# ControlDevBoard.net
KiCad netlist of a schematic drawn in EasyEDA
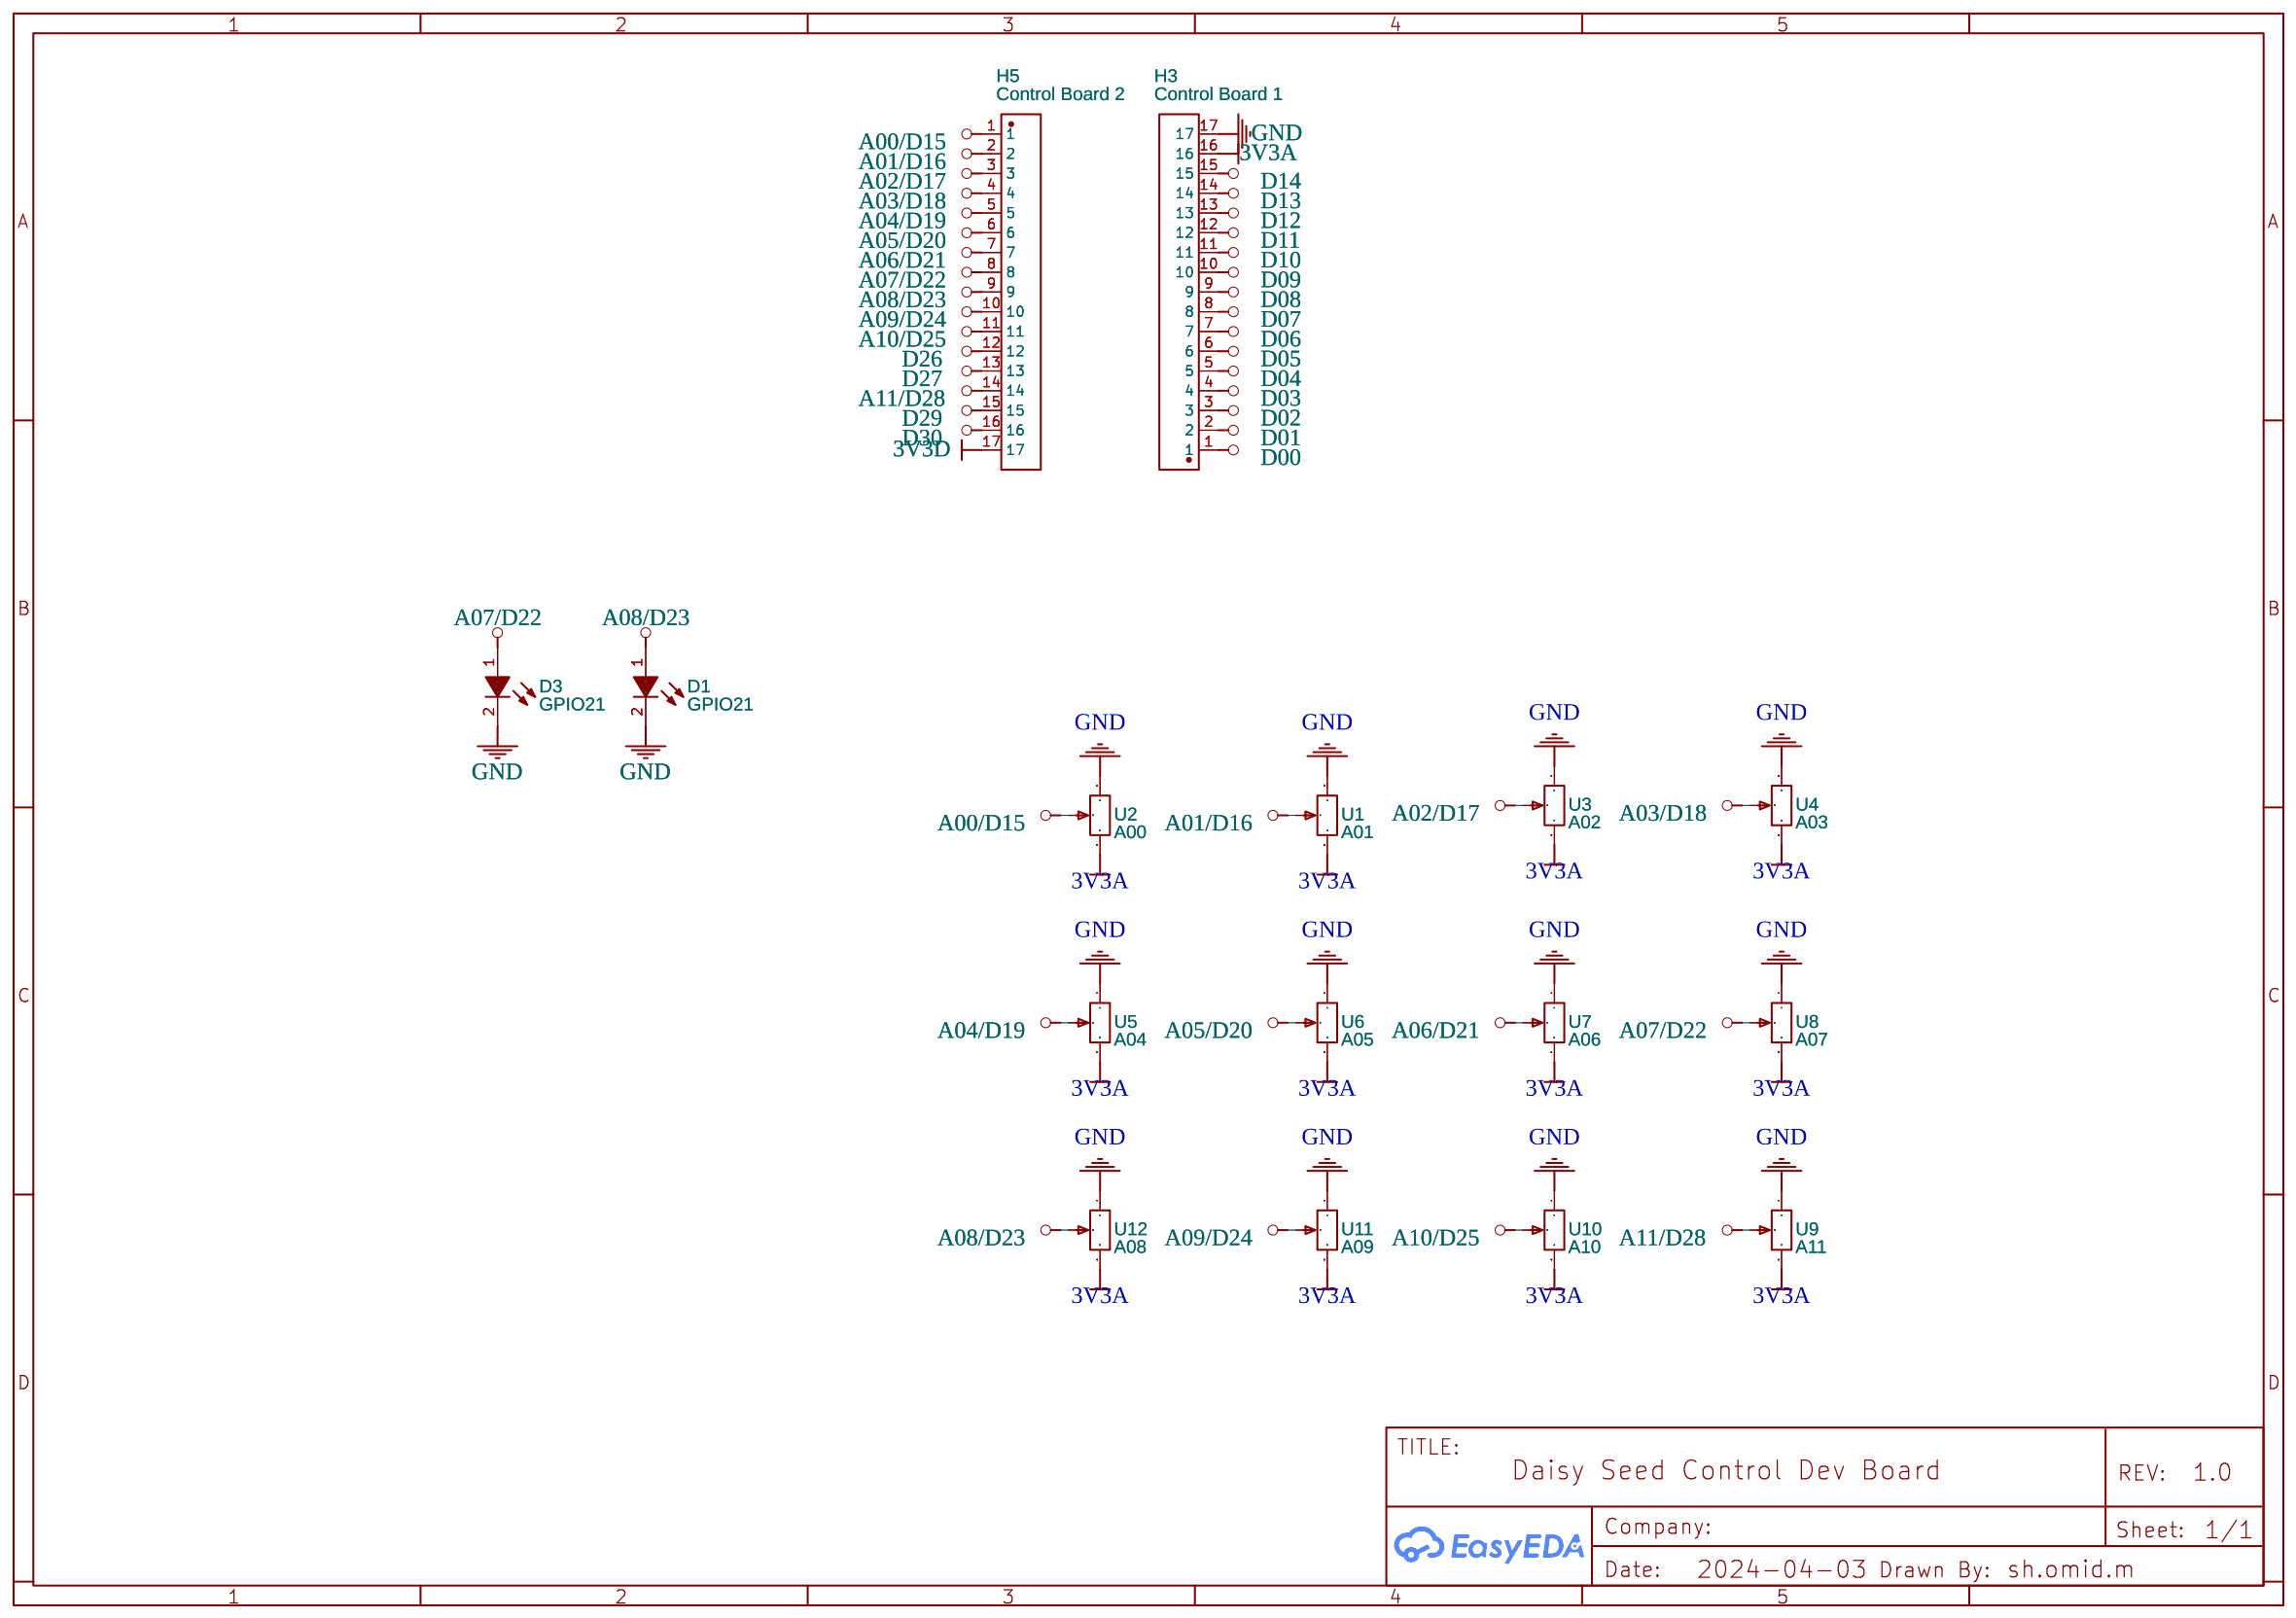
[diagram p0: schematic sheet]

(export (version "E")
  (design (tool "Eeschema 10.0.6"))
  (components
    (comp (ref "D1")
      (value "GPIO21")
      (fields (field (name "Manufacturer Part") "5600") (field (name "Manufacturer") "VccLite"))
      (libsource (lib "") (part "3mm Green TH LED 5600"))
    )
    (comp (ref "D3")
      (value "GPIO21")
      (fields (field (name "Manufacturer Part") "5600") (field (name "Manufacturer") "VccLite"))
      (libsource (lib "") (part "3mm Green TH LED 5600"))
    )
    (comp (ref "H3")
      (value "Control Board 1")
      (fields
        (field (name "Manufacturer Part") "PZ254-1-17-Z-8.5")
        (field (name "Manufacturer") "HCTL(华灿天禄)")
      )
      (libsource (lib "") (part "PZ254-1-17-Z-8.5_1"))
    )
    (comp (ref "H5")
      (value "Control Board 2")
      (fields
        (field (name "Manufacturer Part") "PZ254-1-17-Z-8.5")
        (field (name "Manufacturer") "HCTL(华灿天禄)")
      )
      (libsource (lib "") (part "PZ254-1-17-Z-8.5"))
    )
    (comp (ref "U1")
      (value "A01")
      (fields (field (name "Manufacturer Part") "EVND8AA03B13"))
      (libsource (lib "") (part "Potentiometer"))
    )
    (comp (ref "U2")
      (value "A00")
      (fields (field (name "Manufacturer Part") "EVND8AA03B13"))
      (libsource (lib "") (part "Potentiometer"))
    )
    (comp (ref "U3")
      (value "A02")
      (fields (field (name "Manufacturer Part") "EVND8AA03B13"))
      (libsource (lib "") (part "Potentiometer"))
    )
    (comp (ref "U4")
      (value "A03")
      (fields (field (name "Manufacturer Part") "EVND8AA03B13"))
      (libsource (lib "") (part "Potentiometer"))
    )
    (comp (ref "U5")
      (value "A04")
      (fields (field (name "Manufacturer Part") "EVND8AA03B13"))
      (libsource (lib "") (part "Potentiometer"))
    )
    (comp (ref "U6")
      (value "A05")
      (fields (field (name "Manufacturer Part") "EVND8AA03B13"))
      (libsource (lib "") (part "Potentiometer"))
    )
    (comp (ref "U7")
      (value "A06")
      (fields (field (name "Manufacturer Part") "EVND8AA03B13"))
      (libsource (lib "") (part "Potentiometer"))
    )
    (comp (ref "U8")
      (value "A07")
      (fields (field (name "Manufacturer Part") "EVND8AA03B13"))
      (libsource (lib "") (part "Potentiometer"))
    )
    (comp (ref "U9")
      (value "A11")
      (fields (field (name "Manufacturer Part") "EVND8AA03B13"))
      (libsource (lib "") (part "Potentiometer"))
    )
    (comp (ref "U10")
      (value "A10")
      (fields (field (name "Manufacturer Part") "EVND8AA03B13"))
      (libsource (lib "") (part "Potentiometer"))
    )
    (comp (ref "U11")
      (value "A09")
      (fields (field (name "Manufacturer Part") "EVND8AA03B13"))
      (libsource (lib "") (part "Potentiometer"))
    )
    (comp (ref "U12")
      (value "A08")
      (fields (field (name "Manufacturer Part") "EVND8AA03B13"))
      (libsource (lib "") (part "Potentiometer"))
    )
  )
  (nets
    (net (code "1") (name "3V3A") (class "Default")
      (node (ref "H3") (pin "16") (pinfunction "16_16") (pintype "unspecified"))
      (node (ref "U1") (pin "3") (pinfunction "3_3") (pintype "input"))
      (node (ref "U10") (pin "3") (pinfunction "3_3") (pintype "input"))
      (node (ref "U11") (pin "3") (pinfunction "3_3") (pintype "input"))
      (node (ref "U12") (pin "3") (pinfunction "3_3") (pintype "input"))
      (node (ref "U2") (pin "3") (pinfunction "3_3") (pintype "input"))
      (node (ref "U3") (pin "3") (pinfunction "3_3") (pintype "input"))
      (node (ref "U4") (pin "3") (pinfunction "3_3") (pintype "input"))
      (node (ref "U5") (pin "3") (pinfunction "3_3") (pintype "input"))
      (node (ref "U6") (pin "3") (pinfunction "3_3") (pintype "input"))
      (node (ref "U7") (pin "3") (pinfunction "3_3") (pintype "input"))
      (node (ref "U8") (pin "3") (pinfunction "3_3") (pintype "input"))
      (node (ref "U9") (pin "3") (pinfunction "3_3") (pintype "input"))
    )
    (net (code "2") (name "3V3D") (class "Default")
      (node (ref "H5") (pin "17") (pinfunction "17_17") (pintype "unspecified"))
    )
    (net (code "3") (name "A00{slash}D15") (class "Default")
      (node (ref "H5") (pin "1") (pinfunction "1_1") (pintype "unspecified"))
      (node (ref "U2") (pin "2") (pinfunction "2_2") (pintype "input"))
    )
    (net (code "4") (name "A01{slash}D16") (class "Default")
      (node (ref "H5") (pin "2") (pinfunction "2_2") (pintype "unspecified"))
      (node (ref "U1") (pin "2") (pinfunction "2_2") (pintype "input"))
    )
    (net (code "5") (name "A02{slash}D17") (class "Default")
      (node (ref "H5") (pin "3") (pinfunction "3_3") (pintype "unspecified"))
      (node (ref "U3") (pin "2") (pinfunction "2_2") (pintype "input"))
    )
    (net (code "6") (name "A03{slash}D18") (class "Default")
      (node (ref "H5") (pin "4") (pinfunction "4_4") (pintype "unspecified"))
      (node (ref "U4") (pin "2") (pinfunction "2_2") (pintype "input"))
    )
    (net (code "7") (name "A04{slash}D19") (class "Default")
      (node (ref "H5") (pin "5") (pinfunction "5_5") (pintype "unspecified"))
      (node (ref "U5") (pin "2") (pinfunction "2_2") (pintype "input"))
    )
    (net (code "8") (name "A05{slash}D20") (class "Default")
      (node (ref "H5") (pin "6") (pinfunction "6_6") (pintype "unspecified"))
      (node (ref "U6") (pin "2") (pinfunction "2_2") (pintype "input"))
    )
    (net (code "9") (name "A06{slash}D21") (class "Default")
      (node (ref "H5") (pin "7") (pinfunction "7_7") (pintype "unspecified"))
      (node (ref "U7") (pin "2") (pinfunction "2_2") (pintype "input"))
    )
    (net (code "10") (name "A07{slash}D22") (class "Default")
      (node (ref "D3") (pin "1") (pinfunction "A_1") (pintype "unspecified"))
      (node (ref "H5") (pin "8") (pinfunction "8_8") (pintype "unspecified"))
      (node (ref "U8") (pin "2") (pinfunction "2_2") (pintype "input"))
    )
    (net (code "11") (name "A08{slash}D23") (class "Default")
      (node (ref "D1") (pin "1") (pinfunction "A_1") (pintype "unspecified"))
      (node (ref "H5") (pin "9") (pinfunction "9_9") (pintype "unspecified"))
      (node (ref "U12") (pin "2") (pinfunction "2_2") (pintype "input"))
    )
    (net (code "12") (name "A09{slash}D24") (class "Default")
      (node (ref "H5") (pin "10") (pinfunction "10_10") (pintype "unspecified"))
      (node (ref "U11") (pin "2") (pinfunction "2_2") (pintype "input"))
    )
    (net (code "13") (name "A10{slash}D25") (class "Default")
      (node (ref "H5") (pin "11") (pinfunction "11_11") (pintype "unspecified"))
      (node (ref "U10") (pin "2") (pinfunction "2_2") (pintype "input"))
    )
    (net (code "14") (name "A11{slash}D28") (class "Default")
      (node (ref "H5") (pin "14") (pinfunction "14_14") (pintype "unspecified"))
      (node (ref "U9") (pin "2") (pinfunction "2_2") (pintype "input"))
    )
    (net (code "15") (name "D00") (class "Default")
      (node (ref "H3") (pin "1") (pinfunction "1_1") (pintype "unspecified"))
    )
    (net (code "16") (name "D01") (class "Default")
      (node (ref "H3") (pin "2") (pinfunction "2_2") (pintype "unspecified"))
    )
    (net (code "17") (name "D02") (class "Default")
      (node (ref "H3") (pin "3") (pinfunction "3_3") (pintype "unspecified"))
    )
    (net (code "18") (name "D03") (class "Default")
      (node (ref "H3") (pin "4") (pinfunction "4_4") (pintype "unspecified"))
    )
    (net (code "19") (name "D04") (class "Default")
      (node (ref "H3") (pin "5") (pinfunction "5_5") (pintype "unspecified"))
    )
    (net (code "20") (name "D05") (class "Default")
      (node (ref "H3") (pin "6") (pinfunction "6_6") (pintype "unspecified"))
    )
    (net (code "21") (name "D06") (class "Default")
      (node (ref "H3") (pin "7") (pinfunction "7_7") (pintype "unspecified"))
    )
    (net (code "22") (name "D07") (class "Default")
      (node (ref "H3") (pin "8") (pinfunction "8_8") (pintype "unspecified"))
    )
    (net (code "23") (name "D08") (class "Default")
      (node (ref "H3") (pin "9") (pinfunction "9_9") (pintype "unspecified"))
    )
    (net (code "24") (name "D09") (class "Default")
      (node (ref "H3") (pin "10") (pinfunction "10_10") (pintype "unspecified"))
    )
    (net (code "25") (name "D10") (class "Default")
      (node (ref "H3") (pin "11") (pinfunction "11_11") (pintype "unspecified"))
    )
    (net (code "26") (name "D11") (class "Default")
      (node (ref "H3") (pin "12") (pinfunction "12_12") (pintype "unspecified"))
    )
    (net (code "27") (name "D12") (class "Default")
      (node (ref "H3") (pin "13") (pinfunction "13_13") (pintype "unspecified"))
    )
    (net (code "28") (name "D13") (class "Default")
      (node (ref "H3") (pin "14") (pinfunction "14_14") (pintype "unspecified"))
    )
    (net (code "29") (name "D14") (class "Default")
      (node (ref "H3") (pin "15") (pinfunction "15_15") (pintype "unspecified"))
    )
    (net (code "30") (name "D26") (class "Default")
      (node (ref "H5") (pin "12") (pinfunction "12_12") (pintype "unspecified"))
    )
    (net (code "31") (name "D27") (class "Default")
      (node (ref "H5") (pin "13") (pinfunction "13_13") (pintype "unspecified"))
    )
    (net (code "32") (name "D29") (class "Default")
      (node (ref "H5") (pin "15") (pinfunction "15_15") (pintype "unspecified"))
    )
    (net (code "33") (name "D30") (class "Default")
      (node (ref "H5") (pin "16") (pinfunction "16_16") (pintype "unspecified"))
    )
    (net (code "34") (name "GND") (class "Default")
      (node (ref "D1") (pin "2") (pinfunction "K_2") (pintype "unspecified"))
      (node (ref "D3") (pin "2") (pinfunction "K_2") (pintype "unspecified"))
      (node (ref "H3") (pin "17") (pinfunction "17_17") (pintype "unspecified"))
      (node (ref "U1") (pin "1") (pinfunction "1_1") (pintype "input"))
      (node (ref "U10") (pin "1") (pinfunction "1_1") (pintype "input"))
      (node (ref "U11") (pin "1") (pinfunction "1_1") (pintype "input"))
      (node (ref "U12") (pin "1") (pinfunction "1_1") (pintype "input"))
      (node (ref "U2") (pin "1") (pinfunction "1_1") (pintype "input"))
      (node (ref "U3") (pin "1") (pinfunction "1_1") (pintype "input"))
      (node (ref "U4") (pin "1") (pinfunction "1_1") (pintype "input"))
      (node (ref "U5") (pin "1") (pinfunction "1_1") (pintype "input"))
      (node (ref "U6") (pin "1") (pinfunction "1_1") (pintype "input"))
      (node (ref "U7") (pin "1") (pinfunction "1_1") (pintype "input"))
      (node (ref "U8") (pin "1") (pinfunction "1_1") (pintype "input"))
      (node (ref "U9") (pin "1") (pinfunction "1_1") (pintype "input"))
    )
  )
)
